# alimentation_220V.net
KiCad netlist of a schematic drawn in EAGLE
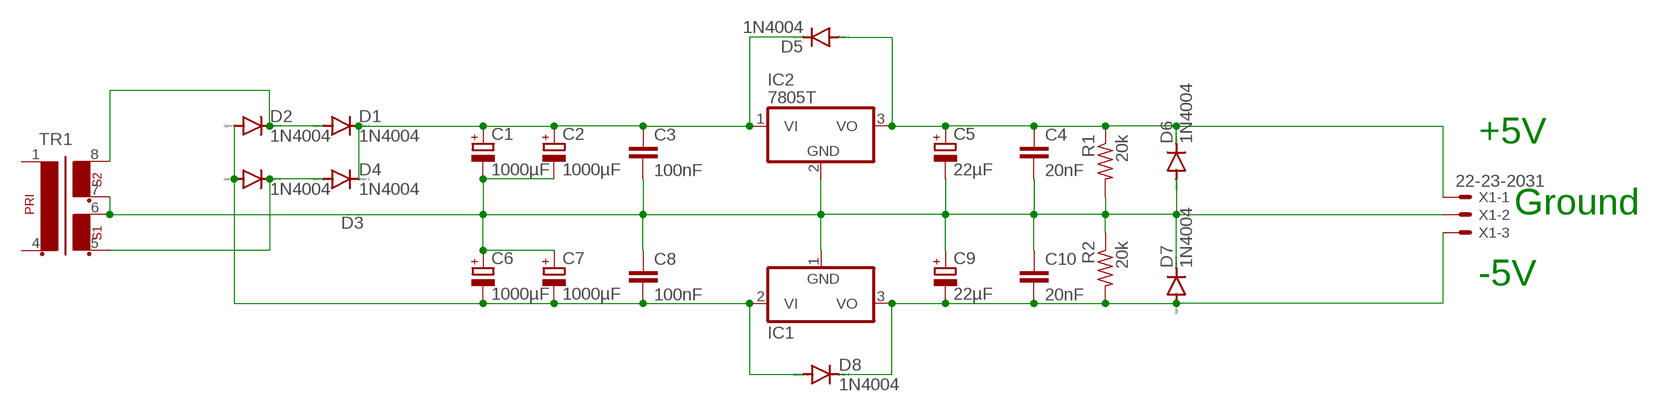
[diagram p0: schematic, sheet 1]

(export (version "E")
  (design (tool "Eeschema 10.0.6"))
  (components
    (comp (ref "C1")
      (value "1000µF")
      (footprint "eagle-import:140CLH-0810")
      (libsource (lib "eagle-import") (part "CPOL-EU140CLH-0810"))
    )
    (comp (ref "C2")
      (value "1000µF")
      (footprint "eagle-import:140CLH-0810")
      (libsource (lib "eagle-import") (part "CPOL-EU140CLH-0810"))
    )
    (comp (ref "C3")
      (value "100nF")
      (footprint "eagle-import:C2.5-3")
      (libsource (lib "eagle-import") (part "C2,5-3"))
    )
    (comp (ref "C4")
      (value "20nF")
      (footprint "eagle-import:C2.5-3")
      (libsource (lib "eagle-import") (part "C2,5-3"))
    )
    (comp (ref "C5")
      (value "22µF")
      (footprint "eagle-import:140CLH-0810")
      (libsource (lib "eagle-import") (part "CPOL-EU140CLH-0810"))
    )
    (comp (ref "C6")
      (value "1000µF")
      (footprint "eagle-import:140CLH-0810")
      (libsource (lib "eagle-import") (part "CPOL-EU140CLH-0810"))
    )
    (comp (ref "C7")
      (value "1000µF")
      (footprint "eagle-import:140CLH-0810")
      (libsource (lib "eagle-import") (part "CPOL-EU140CLH-0810"))
    )
    (comp (ref "C8")
      (value "100nF")
      (footprint "eagle-import:C2.5-3")
      (libsource (lib "eagle-import") (part "C2,5-3"))
    )
    (comp (ref "C9")
      (value "22µF")
      (footprint "eagle-import:140CLH-0810")
      (libsource (lib "eagle-import") (part "CPOL-EU140CLH-0810"))
    )
    (comp (ref "C10")
      (value "20nF")
      (footprint "eagle-import:C2.5-3")
      (libsource (lib "eagle-import") (part "C2,5-3"))
    )
    (comp (ref "D1")
      (value "1N4004")
      (footprint "eagle-import:DO41-10")
      (libsource (lib "eagle-import") (part "1N4004"))
    )
    (comp (ref "D2")
      (value "1N4004")
      (footprint "eagle-import:DO41-10")
      (libsource (lib "eagle-import") (part "1N4004"))
    )
    (comp (ref "D3")
      (value "1N4004")
      (footprint "eagle-import:DO41-10")
      (libsource (lib "eagle-import") (part "1N4004"))
    )
    (comp (ref "D4")
      (value "1N4004")
      (footprint "eagle-import:DO41-10")
      (libsource (lib "eagle-import") (part "1N4004"))
    )
    (comp (ref "D5")
      (value "1N4004")
      (footprint "eagle-import:DO41-10")
      (libsource (lib "eagle-import") (part "1N4004"))
    )
    (comp (ref "D6")
      (value "1N4004")
      (footprint "eagle-import:DO41-10")
      (libsource (lib "eagle-import") (part "1N4004"))
    )
    (comp (ref "D7")
      (value "1N4004")
      (footprint "eagle-import:DO41-10")
      (libsource (lib "eagle-import") (part "1N4004"))
    )
    (comp (ref "D8")
      (value "1N4004")
      (footprint "eagle-import:DO41-10")
      (libsource (lib "eagle-import") (part "1N4004"))
    )
    (comp (ref "IC1")
      (value "7905T")
      (footprint "eagle-import:TO220H")
      (libsource (lib "eagle-import") (part "79T05"))
    )
    (comp (ref "IC2")
      (value "7805T")
      (footprint "eagle-import:TO220H")
      (libsource (lib "eagle-import") (part "78T05"))
    )
    (comp (ref "R1")
      (value "20k")
      (footprint "eagle-import:0204_7")
      (libsource (lib "eagle-import") (part "R-US_0204/7"))
    )
    (comp (ref "R2")
      (value "20k")
      (footprint "eagle-import:0204_7")
      (libsource (lib "eagle-import") (part "R-US_0204/7"))
    )
    (comp (ref "TR1")
      (value "EE20-2")
      (footprint "eagle-import:EE20-2")
      (libsource (lib "eagle-import") (part "EE20-2"))
    )
    (comp (ref "X1")
      (value "22-23-2031")
      (footprint "eagle-import:22-23-2031")
      (fields (field (name "MF") "MOLEX"))
      (libsource (lib "eagle-import") (part "22-23-2031"))
    )
  )
  (nets
    (net (code "1") (name "Net-(IC1-GND)") (class "Default")
      (node (ref "C1") (pin "-") (pinfunction "-_-") (pintype "passive"))
      (node (ref "C10") (pin "1") (pinfunction "1_1") (pintype "passive"))
      (node (ref "C2") (pin "-") (pinfunction "-_-") (pintype "passive"))
      (node (ref "C3") (pin "2") (pinfunction "2_2") (pintype "passive"))
      (node (ref "C4") (pin "2") (pinfunction "2_2") (pintype "passive"))
      (node (ref "C5") (pin "-") (pinfunction "-_-") (pintype "passive"))
      (node (ref "C6") (pin "+") (pinfunction "+_+") (pintype "passive"))
      (node (ref "C7") (pin "+") (pinfunction "+_+") (pintype "passive"))
      (node (ref "C8") (pin "1") (pinfunction "1_1") (pintype "passive"))
      (node (ref "C9") (pin "+") (pinfunction "+_+") (pintype "passive"))
      (node (ref "D6") (pin "A") (pinfunction "A_A") (pintype "passive"))
      (node (ref "D7") (pin "C") (pinfunction "C_C") (pintype "passive"))
      (node (ref "IC1") (pin "1") (pinfunction "GND_1") (pintype "passive"))
      (node (ref "IC2") (pin "2") (pinfunction "GND_2") (pintype "passive"))
      (node (ref "R1") (pin "2") (pinfunction "2_2") (pintype "passive"))
      (node (ref "R2") (pin "1") (pinfunction "1_1") (pintype "passive"))
      (node (ref "TR1") (pin "6") (pinfunction "4_6") (pintype "passive"))
      (node (ref "TR1") (pin "7") (pinfunction "5_7") (pintype "passive"))
      (node (ref "X1") (pin "2") (pinfunction "S_2") (pintype "passive"))
    )
    (net (code "2") (name "Net-(IC1-VI)") (class "Default")
      (node (ref "C6") (pin "-") (pinfunction "-_-") (pintype "passive"))
      (node (ref "C7") (pin "-") (pinfunction "-_-") (pintype "passive"))
      (node (ref "C8") (pin "2") (pinfunction "2_2") (pintype "passive"))
      (node (ref "D2") (pin "A") (pinfunction "A_A") (pintype "passive"))
      (node (ref "D3") (pin "A") (pinfunction "A_A") (pintype "passive"))
      (node (ref "D8") (pin "A") (pinfunction "A_A") (pintype "passive"))
      (node (ref "IC1") (pin "2") (pinfunction "VI_2") (pintype "input"))
    )
    (net (code "3") (name "Net-(IC1-VO)") (class "Default")
      (node (ref "C10") (pin "2") (pinfunction "2_2") (pintype "passive"))
      (node (ref "C9") (pin "-") (pinfunction "-_-") (pintype "passive"))
      (node (ref "D7") (pin "A") (pinfunction "A_A") (pintype "passive"))
      (node (ref "D8") (pin "C") (pinfunction "C_C") (pintype "passive"))
      (node (ref "IC1") (pin "3") (pinfunction "VO_3") (pintype "passive"))
      (node (ref "R2") (pin "2") (pinfunction "2_2") (pintype "passive"))
      (node (ref "X1") (pin "3") (pinfunction "S_3") (pintype "passive"))
    )
    (net (code "4") (name "Net-(IC2-VI)") (class "Default")
      (node (ref "C1") (pin "+") (pinfunction "+_+") (pintype "passive"))
      (node (ref "C2") (pin "+") (pinfunction "+_+") (pintype "passive"))
      (node (ref "C3") (pin "1") (pinfunction "1_1") (pintype "passive"))
      (node (ref "D1") (pin "C") (pinfunction "C_C") (pintype "passive"))
      (node (ref "D4") (pin "C") (pinfunction "C_C") (pintype "passive"))
      (node (ref "D5") (pin "C") (pinfunction "C_C") (pintype "passive"))
      (node (ref "IC2") (pin "1") (pinfunction "VI_1") (pintype "input"))
    )
    (net (code "5") (name "Net-(IC2-VO)") (class "Default")
      (node (ref "C4") (pin "1") (pinfunction "1_1") (pintype "passive"))
      (node (ref "C5") (pin "+") (pinfunction "+_+") (pintype "passive"))
      (node (ref "D5") (pin "A") (pinfunction "A_A") (pintype "passive"))
      (node (ref "D6") (pin "C") (pinfunction "C_C") (pintype "passive"))
      (node (ref "IC2") (pin "3") (pinfunction "VO_3") (pintype "passive"))
      (node (ref "R1") (pin "1") (pinfunction "1_1") (pintype "passive"))
      (node (ref "X1") (pin "1") (pinfunction "S_1") (pintype "passive"))
    )
    (net (code "6") (name "Net-(TR1-3)") (class "Default")
      (node (ref "D3") (pin "C") (pinfunction "C_C") (pintype "passive"))
      (node (ref "D4") (pin "A") (pinfunction "A_A") (pintype "passive"))
      (node (ref "TR1") (pin "5") (pinfunction "3_5") (pintype "passive"))
    )
    (net (code "7") (name "Net-(TR1-6)") (class "Default")
      (node (ref "D1") (pin "A") (pinfunction "A_A") (pintype "passive"))
      (node (ref "D2") (pin "C") (pinfunction "C_C") (pintype "passive"))
      (node (ref "TR1") (pin "8") (pinfunction "6_8") (pintype "passive"))
    )
    (net (code "8") (name "unconnected-(TR1-2-Pad4)") (class "Default")
      (node (ref "TR1") (pin "4") (pinfunction "2_4") (pintype "passive"))
    )
    (net (code "9") (name "unconnected-(TR1-Pad1)") (class "Default")
      (node (ref "TR1") (pin "1") (pinfunction "1_1") (pintype "passive"))
    )
  )
)
